# 2_STM32KIT_UART.net
KiCad netlist of a schematic drawn in Altium Designer
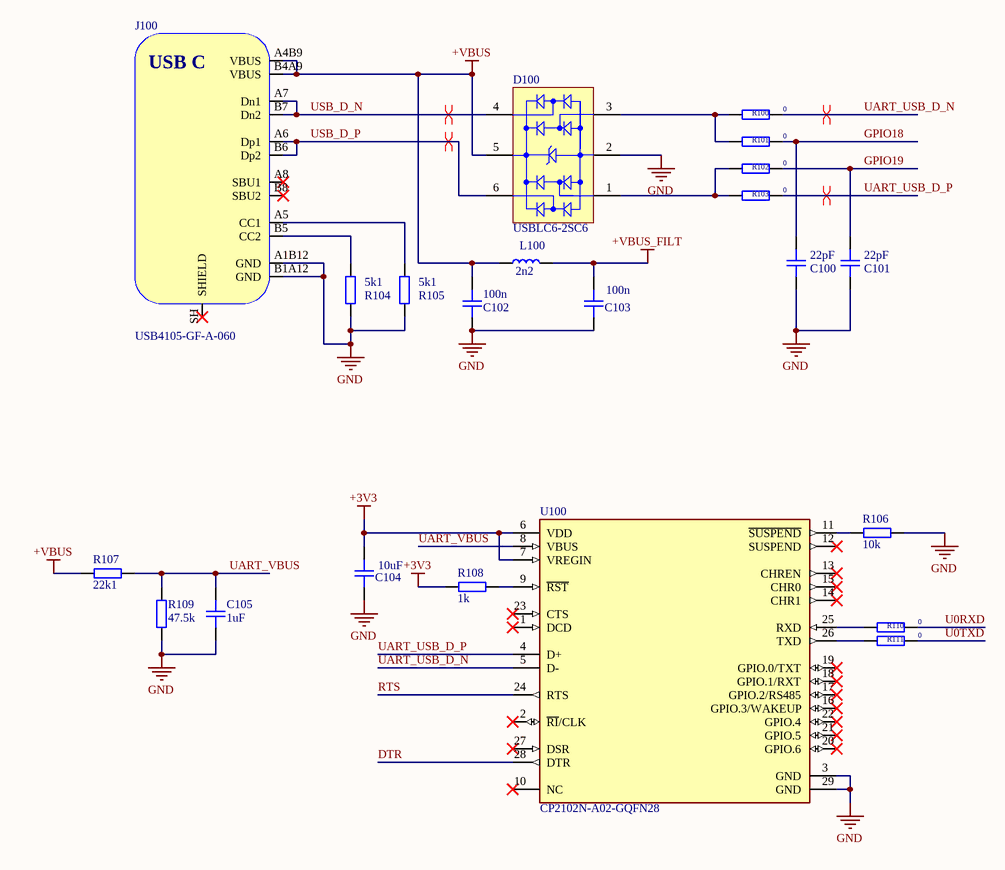
[diagram p0: 2_STM32KIT_UART.SchDoc]

(export (version "E")
  (design (tool "Eeschema 10.0.6"))
  (components
    (comp (ref "C100")
      (value "22pF")
      (footprint "CAP_0402")
      (description "Capacitor SMD 0402")
      (fields (field (name "SOURCE") "Schematic-Lib-PhilsLab.SchLib"))
      (libsource (lib "Industrial University of Ho Chi Minh City") (part "CAP_EL_NP_5MM"))
    )
    (comp (ref "C101")
      (value "22pF")
      (footprint "CAP_0402")
      (description "Capacitor SMD 0402")
      (fields (field (name "SOURCE") "Schematic-Lib-PhilsLab.SchLib"))
      (libsource (lib "Industrial University of Ho Chi Minh City") (part "CAP_EL_NP_5MM"))
    )
    (comp (ref "C102")
      (value "100n")
      (footprint "CAP_0603")
      (description "Capacitor SMD 0603")
      (fields (field (name "SOURCE") "Schematic-Lib-PhilsLab.SchLib"))
      (libsource (lib "Industrial University of Ho Chi Minh City") (part "CAP_EL_NP_5MM"))
    )
    (comp (ref "C103")
      (value "100n")
      (footprint "CAP_0603")
      (description "Capacitor SMD 0603")
      (fields (field (name "SOURCE") "Schematic-Lib-PhilsLab.SchLib"))
      (libsource (lib "Industrial University of Ho Chi Minh City") (part "CAP_EL_NP_5MM"))
    )
    (comp (ref "C104")
      (value "10uF")
      (footprint "CAP_0402")
      (description "Capacitor SMD 0402")
      (fields (field (name "SOURCE") "Schematic-Lib-PhilsLab.SchLib"))
      (libsource (lib "Industrial University of Ho Chi Minh City") (part "CAP_EL_NP_5MM"))
    )
    (comp (ref "C105")
      (value "1uF")
      (footprint "CAP_0402")
      (description "Capacitor SMD 0402")
      (fields (field (name "SOURCE") "Schematic-Lib-PhilsLab.SchLib"))
      (libsource (lib "Industrial University of Ho Chi Minh City") (part "CAP_EL_NP_5MM"))
    )
    (comp (ref "D100")
      (value "USBLC6-2SC6")
      (footprint "STM-SOT23-6L_V")
      (description "Very low capacitance ESD protection, 3.5 pF, -40 to 125 degC, 6-Pin SOT23, RoHS, Tape and Reel")
      (fields (field (name "MANUFACTURER") "STMicroelectronics"))
      (libsource (lib "Altium Content Vault") (part "STM-USB_DVI_HDMIULC6-4SC6X-SOT23-6L"))
    )
    (comp (ref "J100")
      (value "USB4105-GF-A-060")
      (footprint "USB4105-GF-A-060")
      (description "USB Connector Type C SMT 12 Pin")
      (fields (field (name "MANUFACTURER") "GCT") (field (name "SOURCE") "Schematic-Lib-PhilsLab.SchLib"))
      (libsource (lib "Industrial University of Ho Chi Minh City") (part "USB4105-GF-A-060"))
    )
    (comp (ref "L100")
      (value "2n2")
      (footprint "IND_0603")
      (description "Inductor SMD 0603")
      (fields (field (name "SOURCE") "Schematic-Lib-PhilsLab.SchLib"))
      (libsource (lib "Industrial University of Ho Chi Minh City") (part "ASPI-0630HI-6R8M-T15"))
    )
    (comp (ref "R100")
      (value "0")
      (footprint "RES_0402")
      (description "Resistor SMD 0402")
      (fields (field (name "SOURCE") "Schematic-Lib-PhilsLab.SchLib"))
      (libsource (lib "Industrial University of Ho Chi Minh City") (part "RES_5931"))
    )
    (comp (ref "R101")
      (value "0")
      (footprint "RES_0402")
      (description "Resistor SMD 0402")
      (fields (field (name "SOURCE") "Schematic-Lib-PhilsLab.SchLib"))
      (libsource (lib "Industrial University of Ho Chi Minh City") (part "RES_5931"))
    )
    (comp (ref "R102")
      (value "0")
      (footprint "RES_0402")
      (description "Resistor SMD 0402")
      (fields (field (name "SOURCE") "Schematic-Lib-PhilsLab.SchLib"))
      (libsource (lib "Industrial University of Ho Chi Minh City") (part "RES_5931"))
    )
    (comp (ref "R103")
      (value "0")
      (footprint "RES_0402")
      (description "Resistor SMD 0402")
      (fields (field (name "SOURCE") "Schematic-Lib-PhilsLab.SchLib"))
      (libsource (lib "Industrial University of Ho Chi Minh City") (part "RES_5931"))
    )
    (comp (ref "R104")
      (value "5k1")
      (footprint "RES_0603")
      (description "Resistor SMD 0603")
      (fields (field (name "SOURCE") "Schematic-Lib-PhilsLab.SchLib"))
      (libsource (lib "Industrial University of Ho Chi Minh City") (part "RES_5931"))
    )
    (comp (ref "R105")
      (value "5k1")
      (footprint "RES_0603")
      (description "Resistor SMD 0603")
      (fields (field (name "SOURCE") "Schematic-Lib-PhilsLab.SchLib"))
      (libsource (lib "Industrial University of Ho Chi Minh City") (part "RES_5931"))
    )
    (comp (ref "R106")
      (value "10k")
      (footprint "RES_0402")
      (description "Resistor SMD 0402")
      (fields (field (name "SOURCE") "Schematic-Lib-PhilsLab.SchLib"))
      (libsource (lib "Industrial University of Ho Chi Minh City") (part "RES_5931"))
    )
    (comp (ref "R107")
      (value "22k1")
      (footprint "RES_0402")
      (description "Resistor SMD 0402")
      (fields (field (name "SOURCE") "Schematic-Lib-PhilsLab.SchLib"))
      (libsource (lib "Industrial University of Ho Chi Minh City") (part "RES_5931"))
    )
    (comp (ref "R108")
      (value "1k")
      (footprint "RES_0402")
      (description "Resistor SMD 0402")
      (fields (field (name "SOURCE") "Schematic-Lib-PhilsLab.SchLib"))
      (libsource (lib "Industrial University of Ho Chi Minh City") (part "RES_5931"))
    )
    (comp (ref "R109")
      (value "47.5k")
      (footprint "RES_0402")
      (description "Resistor SMD 0402")
      (fields (field (name "SOURCE") "Schematic-Lib-PhilsLab.SchLib"))
      (libsource (lib "Industrial University of Ho Chi Minh City") (part "RES_5931"))
    )
    (comp (ref "R110")
      (value "0")
      (footprint "RES_0402")
      (description "Resistor SMD 0402")
      (fields (field (name "SOURCE") "Schematic-Lib-PhilsLab.SchLib"))
      (libsource (lib "Industrial University of Ho Chi Minh City") (part "RES_5931"))
    )
    (comp (ref "R111")
      (value "0")
      (footprint "RES_0402")
      (description "Resistor SMD 0402")
      (fields (field (name "SOURCE") "Schematic-Lib-PhilsLab.SchLib"))
      (libsource (lib "Industrial University of Ho Chi Minh City") (part "RES_5931"))
    )
    (comp (ref "U100")
      (value "CP2102N-A02-GQFN28")
      (footprint "FP-CP2102N-A02-GQFN28-MFG")
      (description "IC USB TO UART BRIDGE QFN28")
      (libsource (lib "Altium Content Vault") (part "f8fb43f618a03b32512863a7a8093b6"))
    )
  )
  (nets
    (net (code "1") (name "+3V3") (class "Default")
      (node (ref "C104") (pin "2") (pinfunction "2_2") (pintype "passive"))
      (node (ref "R108") (pin "1") (pinfunction "1_1") (pintype "passive"))
      (node (ref "U100") (pin "6") (pinfunction "VDD_6") (pintype "power_in"))
      (node (ref "U100") (pin "7") (pinfunction "VREGIN_7") (pintype "input"))
    )
    (net (code "2") (name "+VBUS") (class "Default")
      (node (ref "C102") (pin "2") (pinfunction "2_2") (pintype "passive"))
      (node (ref "D100") (pin "5") (pinfunction "VBUS_5") (pintype "passive"))
      (node (ref "J100") (pin "A4B9") (pinfunction "VBUS_A4B9") (pintype "passive"))
      (node (ref "J100") (pin "B4A9") (pinfunction "VBUS_B4A9") (pintype "passive"))
      (node (ref "L100") (pin "1") (pinfunction "1_1") (pintype "passive"))
      (node (ref "R107") (pin "2") (pinfunction "2_2") (pintype "passive"))
    )
    (net (code "3") (name "+VBUS_FILT") (class "Default")
      (node (ref "C103") (pin "2") (pinfunction "2_2") (pintype "passive"))
      (node (ref "L100") (pin "2") (pinfunction "2_2") (pintype "passive"))
    )
    (net (code "4") (name "/DTR") (class "Default")
      (node (ref "U100") (pin "28") (pinfunction "DTR_28") (pintype "output"))
    )
    (net (code "5") (name "/GPIO18") (class "Default")
      (node (ref "C100") (pin "2") (pinfunction "2_2") (pintype "passive"))
      (node (ref "R101") (pin "2") (pinfunction "2_2") (pintype "passive"))
    )
    (net (code "6") (name "/GPIO19") (class "Default")
      (node (ref "C101") (pin "2") (pinfunction "2_2") (pintype "passive"))
      (node (ref "R102") (pin "2") (pinfunction "2_2") (pintype "passive"))
    )
    (net (code "7") (name "/RTS") (class "Default")
      (node (ref "U100") (pin "24") (pinfunction "RTS_24") (pintype "output"))
    )
    (net (code "8") (name "/U0RXD") (class "Default")
      (node (ref "R110") (pin "2") (pinfunction "2_2") (pintype "passive"))
    )
    (net (code "9") (name "/U0TXD") (class "Default")
      (node (ref "R111") (pin "2") (pinfunction "2_2") (pintype "passive"))
    )
    (net (code "10") (name "/UART_USB_D_N") (class "Default")
      (node (ref "R100") (pin "2") (pinfunction "2_2") (pintype "passive"))
      (node (ref "U100") (pin "5") (pinfunction "D-_5") (pintype "passive"))
    )
    (net (code "11") (name "/UART_USB_D_P") (class "Default")
      (node (ref "R103") (pin "2") (pinfunction "2_2") (pintype "passive"))
      (node (ref "U100") (pin "4") (pinfunction "D+_4") (pintype "passive"))
    )
    (net (code "12") (name "/UART_VBUS") (class "Default")
      (node (ref "C105") (pin "2") (pinfunction "2_2") (pintype "passive"))
      (node (ref "R107") (pin "1") (pinfunction "1_1") (pintype "passive"))
      (node (ref "R109") (pin "1") (pinfunction "1_1") (pintype "passive"))
      (node (ref "U100") (pin "8") (pinfunction "VBUS_8") (pintype "input"))
    )
    (net (code "13") (name "/USB_D_N") (class "Default")
      (node (ref "D100") (pin "4") (pinfunction "I/O_3_4") (pintype "passive"))
      (node (ref "J100") (pin "A7") (pinfunction "Dn1_A7") (pintype "passive"))
      (node (ref "J100") (pin "B7") (pinfunction "Dn2_B7") (pintype "passive"))
    )
    (net (code "14") (name "/USB_D_P") (class "Default")
      (node (ref "D100") (pin "6") (pinfunction "I/O_4_6") (pintype "passive"))
      (node (ref "J100") (pin "A6") (pinfunction "Dp1_A6") (pintype "passive"))
      (node (ref "J100") (pin "B6") (pinfunction "Dp2_B6") (pintype "passive"))
    )
    (net (code "15") (name "GND") (class "Default")
      (node (ref "C100") (pin "1") (pinfunction "1_1") (pintype "passive"))
      (node (ref "C101") (pin "1") (pinfunction "1_1") (pintype "passive"))
      (node (ref "C102") (pin "1") (pinfunction "1_1") (pintype "passive"))
      (node (ref "C103") (pin "1") (pinfunction "1_1") (pintype "passive"))
      (node (ref "C104") (pin "1") (pinfunction "1_1") (pintype "passive"))
      (node (ref "C105") (pin "1") (pinfunction "1_1") (pintype "passive"))
      (node (ref "D100") (pin "2") (pinfunction "GND_2") (pintype "passive"))
      (node (ref "J100") (pin "A1B12") (pinfunction "GND_A1B12") (pintype "passive"))
      (node (ref "J100") (pin "B1A12") (pinfunction "GND_B1A12") (pintype "passive"))
      (node (ref "R104") (pin "1") (pinfunction "1_1") (pintype "passive"))
      (node (ref "R105") (pin "1") (pinfunction "1_1") (pintype "passive"))
      (node (ref "R106") (pin "2") (pinfunction "2_2") (pintype "passive"))
      (node (ref "R109") (pin "2") (pinfunction "2_2") (pintype "passive"))
      (node (ref "U100") (pin "29") (pinfunction "GND_29") (pintype "power_in"))
      (node (ref "U100") (pin "3") (pinfunction "GND_3") (pintype "power_in"))
    )
    (net (code "16") (name "Net-(D100-I{slash}O_1)") (class "Default")
      (node (ref "D100") (pin "1") (pinfunction "I/O_1_1") (pintype "passive"))
      (node (ref "R102") (pin "1") (pinfunction "1_1") (pintype "passive"))
      (node (ref "R103") (pin "1") (pinfunction "1_1") (pintype "passive"))
    )
    (net (code "17") (name "Net-(D100-I{slash}O_2)") (class "Default")
      (node (ref "D100") (pin "3") (pinfunction "I/O_2_3") (pintype "passive"))
      (node (ref "R100") (pin "1") (pinfunction "1_1") (pintype "passive"))
      (node (ref "R101") (pin "1") (pinfunction "1_1") (pintype "passive"))
    )
    (net (code "18") (name "Net-(J100-CC1)") (class "Default")
      (node (ref "J100") (pin "A5") (pinfunction "CC1_A5") (pintype "passive"))
      (node (ref "R105") (pin "2") (pinfunction "2_2") (pintype "passive"))
    )
    (net (code "19") (name "Net-(J100-CC2)") (class "Default")
      (node (ref "J100") (pin "B5") (pinfunction "CC2_B5") (pintype "passive"))
      (node (ref "R104") (pin "2") (pinfunction "2_2") (pintype "passive"))
    )
    (net (code "20") (name "Net-(U100-RXD)") (class "Default")
      (node (ref "R110") (pin "1") (pinfunction "1_1") (pintype "passive"))
      (node (ref "U100") (pin "25") (pinfunction "RXD_25") (pintype "input"))
    )
    (net (code "21") (name "Net-(U100-TXD)") (class "Default")
      (node (ref "R111") (pin "1") (pinfunction "1_1") (pintype "passive"))
      (node (ref "U100") (pin "26") (pinfunction "TXD_26") (pintype "output"))
    )
    (net (code "22") (name "Net-(U100-~{RST})") (class "Default")
      (node (ref "R108") (pin "2") (pinfunction "2_2") (pintype "passive"))
      (node (ref "U100") (pin "9") (pinfunction "~{RST}_9") (pintype "input"))
    )
    (net (code "23") (name "Net-(U100-~{SUSPEND})") (class "Default")
      (node (ref "R106") (pin "1") (pinfunction "1_1") (pintype "passive"))
      (node (ref "U100") (pin "11") (pinfunction "~{SUSPEND}_11") (pintype "output"))
    )
    (net (code "24") (name "unconnected-(J100-SBU1-PadA8)") (class "Default")
      (node (ref "J100") (pin "A8") (pinfunction "SBU1_A8") (pintype "passive+no_connect"))
    )
    (net (code "25") (name "unconnected-(J100-SBU2-PadB8)") (class "Default")
      (node (ref "J100") (pin "B8") (pinfunction "SBU2_B8") (pintype "passive+no_connect"))
    )
    (net (code "26") (name "unconnected-(J100-SHIELD-PadSH)") (class "Default")
      (node (ref "J100") (pin "SH") (pinfunction "SHIELD_SH") (pintype "passive+no_connect"))
    )
    (net (code "27") (name "unconnected-(U100-CHR0-Pad15)") (class "Default")
      (node (ref "U100") (pin "15") (pinfunction "CHR0_15") (pintype "output+no_connect"))
    )
    (net (code "28") (name "unconnected-(U100-CHR1-Pad14)") (class "Default")
      (node (ref "U100") (pin "14") (pinfunction "CHR1_14") (pintype "output+no_connect"))
    )
    (net (code "29") (name "unconnected-(U100-CHREN-Pad13)") (class "Default")
      (node (ref "U100") (pin "13") (pinfunction "CHREN_13") (pintype "output+no_connect"))
    )
    (net (code "30") (name "unconnected-(U100-CTS-Pad23)") (class "Default")
      (node (ref "U100") (pin "23") (pinfunction "CTS_23") (pintype "input+no_connect"))
    )
    (net (code "31") (name "unconnected-(U100-DCD-Pad1)") (class "Default")
      (node (ref "U100") (pin "1") (pinfunction "DCD_1") (pintype "input+no_connect"))
    )
    (net (code "32") (name "unconnected-(U100-DSR-Pad27)") (class "Default")
      (node (ref "U100") (pin "27") (pinfunction "DSR_27") (pintype "input+no_connect"))
    )
    (net (code "33") (name "unconnected-(U100-GPIO.0{slash}TXT-Pad19)") (class "Default")
      (node (ref "U100") (pin "19") (pinfunction "GPIO.0/TXT_19") (pintype "bidirectional+no_connect"))
    )
    (net (code "34") (name "unconnected-(U100-GPIO.1{slash}RXT-Pad18)") (class "Default")
      (node (ref "U100") (pin "18") (pinfunction "GPIO.1/RXT_18") (pintype "bidirectional+no_connect"))
    )
    (net (code "35") (name "unconnected-(U100-GPIO.2{slash}RS485-Pad17)") (class "Default")
      (node (ref "U100") (pin "17") (pinfunction "GPIO.2/RS485_17") (pintype "bidirectional+no_connect"))
    )
    (net (code "36") (name "unconnected-(U100-GPIO.3{slash}WAKEUP-Pad16)") (class "Default")
      (node (ref "U100") (pin "16") (pinfunction "GPIO.3/WAKEUP_16") (pintype "bidirectional+no_connect"))
    )
    (net (code "37") (name "unconnected-(U100-GPIO.4-Pad22)") (class "Default")
      (node (ref "U100") (pin "22") (pinfunction "GPIO.4_22") (pintype "bidirectional+no_connect"))
    )
    (net (code "38") (name "unconnected-(U100-GPIO.5-Pad21)") (class "Default")
      (node (ref "U100") (pin "21") (pinfunction "GPIO.5_21") (pintype "bidirectional+no_connect"))
    )
    (net (code "39") (name "unconnected-(U100-GPIO.6-Pad20)") (class "Default")
      (node (ref "U100") (pin "20") (pinfunction "GPIO.6_20") (pintype "bidirectional+no_connect"))
    )
    (net (code "40") (name "unconnected-(U100-NC-Pad10)") (class "Default")
      (node (ref "U100") (pin "10") (pinfunction "NC_10") (pintype "passive+no_connect"))
    )
    (net (code "41") (name "unconnected-(U100-SUSPEND-Pad12)") (class "Default")
      (node (ref "U100") (pin "12") (pinfunction "SUSPEND_12") (pintype "output+no_connect"))
    )
    (net (code "42") (name "unconnected-(U100-~{RI}{slash}CLK-Pad2)") (class "Default")
      (node (ref "U100") (pin "2") (pinfunction "~{RI}/CLK_2") (pintype "bidirectional+no_connect"))
    )
  )
)
